# arduino-shield-xyz-stepper-v3.net
KiCad netlist of a schematic drawn in EAGLE
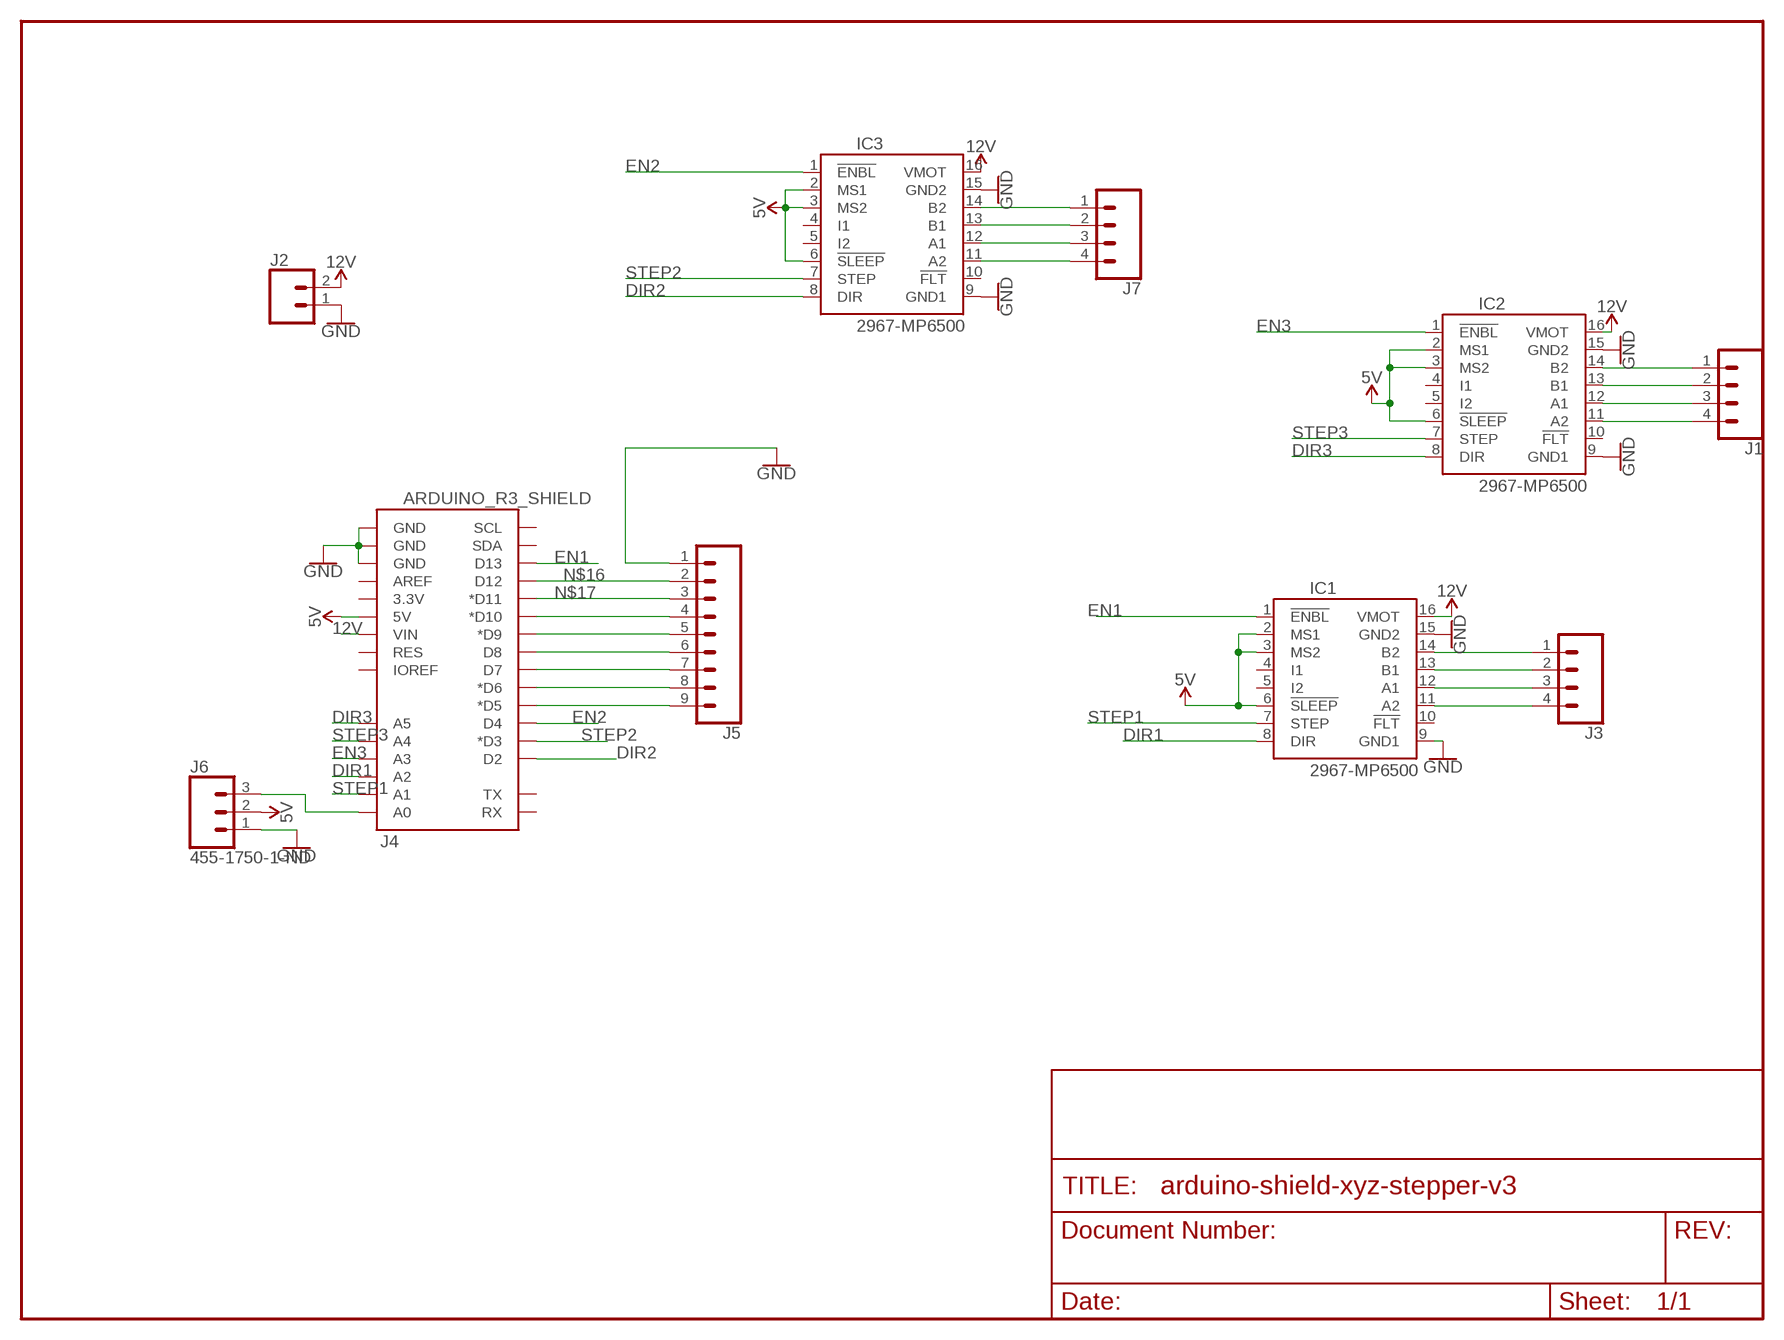
[diagram p0: schematic, sheet 1]

(export (version "E")
  (design (tool "Eeschema 10.0.6"))
  (components
    (comp (ref "IC1")
      (value "2967-MP6500")
      (footprint "eagle-import:MP6500")
      (libsource (lib "eagle-import") (part "2967-MP6500"))
    )
    (comp (ref "IC2")
      (value "2967-MP6500")
      (footprint "eagle-import:MP6500")
      (libsource (lib "eagle-import") (part "2967-MP6500"))
    )
    (comp (ref "IC3")
      (value "2967-MP6500")
      (footprint "eagle-import:MP6500")
      (libsource (lib "eagle-import") (part "2967-MP6500"))
    )
    (comp (ref "J1")
      (value "CONN_04")
      (footprint "eagle-import:1X04")
      (libsource (lib "eagle-import") (part "CONN_04"))
    )
    (comp (ref "J2")
      (value "CONN_02")
      (footprint "eagle-import:1X02")
      (libsource (lib "eagle-import") (part "CONN_02"))
    )
    (comp (ref "J3")
      (value "CONN_04")
      (footprint "eagle-import:1X04")
      (libsource (lib "eagle-import") (part "CONN_04"))
    )
    (comp (ref "J4")
      (value "ARDUINO_R3_SHIELD")
      (footprint "eagle-import:UNO_R3_SHIELD")
      (libsource (lib "eagle-import") (part "ARDUINO_R3_SHIELD"))
    )
    (comp (ref "J5")
      (value "CONN_09")
      (footprint "eagle-import:1X09")
      (libsource (lib "eagle-import") (part "CONN_09"))
    )
    (comp (ref "J6")
      (value "455-1750-1-ND")
      (footprint "eagle-import:1X03")
      (libsource (lib "eagle-import") (part "CONN_03"))
    )
    (comp (ref "J7")
      (value "CONN_04")
      (footprint "eagle-import:1X04")
      (libsource (lib "eagle-import") (part "CONN_04"))
    )
  )
  (nets
    (net (code "1") (name "/DIR1") (class "Default")
      (node (ref "IC1") (pin "8") (pinfunction "DIR_8") (pintype "input"))
      (node (ref "J4") (pin "A2") (pinfunction "A2_A2") (pintype "bidirectional"))
    )
    (net (code "2") (name "/DIR2") (class "Default")
      (node (ref "IC3") (pin "8") (pinfunction "DIR_8") (pintype "input"))
      (node (ref "J4") (pin "D2") (pinfunction "D2_D2") (pintype "bidirectional"))
    )
    (net (code "3") (name "/DIR3") (class "Default")
      (node (ref "IC2") (pin "8") (pinfunction "DIR_8") (pintype "input"))
      (node (ref "J4") (pin "A5") (pinfunction "A5_A5") (pintype "bidirectional"))
    )
    (net (code "4") (name "/EN1") (class "Default")
      (node (ref "IC1") (pin "1") (pinfunction "~{ENBL}_1") (pintype "passive"))
      (node (ref "J4") (pin "D13") (pinfunction "D13_D13") (pintype "bidirectional"))
    )
    (net (code "5") (name "/EN2") (class "Default")
      (node (ref "IC3") (pin "1") (pinfunction "~{ENBL}_1") (pintype "passive"))
      (node (ref "J4") (pin "D4") (pinfunction "D4_D4") (pintype "bidirectional"))
    )
    (net (code "6") (name "/EN3") (class "Default")
      (node (ref "IC2") (pin "1") (pinfunction "~{ENBL}_1") (pintype "passive"))
      (node (ref "J4") (pin "A3") (pinfunction "A3_A3") (pintype "bidirectional"))
    )
    (net (code "7") (name "/N$16") (class "Default")
      (node (ref "J4") (pin "D12") (pinfunction "D12_D12") (pintype "bidirectional"))
      (node (ref "J5") (pin "2") (pinfunction "2_2") (pintype "passive"))
    )
    (net (code "8") (name "/N$17") (class "Default")
      (node (ref "J4") (pin "D11") (pinfunction "*D11_D11") (pintype "bidirectional"))
      (node (ref "J5") (pin "3") (pinfunction "3_3") (pintype "passive"))
    )
    (net (code "9") (name "/STEP1") (class "Default")
      (node (ref "IC1") (pin "7") (pinfunction "STEP_7") (pintype "input"))
      (node (ref "J4") (pin "A1") (pinfunction "A1_A1") (pintype "bidirectional"))
    )
    (net (code "10") (name "/STEP2") (class "Default")
      (node (ref "IC3") (pin "7") (pinfunction "STEP_7") (pintype "input"))
      (node (ref "J4") (pin "D3") (pinfunction "*D3_D3") (pintype "bidirectional"))
    )
    (net (code "11") (name "/STEP3") (class "Default")
      (node (ref "IC2") (pin "7") (pinfunction "STEP_7") (pintype "input"))
      (node (ref "J4") (pin "A4") (pinfunction "A4_A4") (pintype "bidirectional"))
    )
    (net (code "12") (name "5V") (class "Default")
      (node (ref "IC1") (pin "2") (pinfunction "MS1_2") (pintype "passive"))
      (node (ref "IC1") (pin "3") (pinfunction "MS2_3") (pintype "passive"))
      (node (ref "IC1") (pin "6") (pinfunction "~{SLEEP}_6") (pintype "input"))
      (node (ref "IC2") (pin "2") (pinfunction "MS1_2") (pintype "passive"))
      (node (ref "IC2") (pin "3") (pinfunction "MS2_3") (pintype "passive"))
      (node (ref "IC2") (pin "6") (pinfunction "~{SLEEP}_6") (pintype "input"))
      (node (ref "IC3") (pin "2") (pinfunction "MS1_2") (pintype "passive"))
      (node (ref "IC3") (pin "3") (pinfunction "MS2_3") (pintype "passive"))
      (node (ref "IC3") (pin "6") (pinfunction "~{SLEEP}_6") (pintype "input"))
      (node (ref "J4") (pin "5V") (pinfunction "5V_5V") (pintype "bidirectional"))
      (node (ref "J6") (pin "2") (pinfunction "2_2") (pintype "passive"))
    )
    (net (code "13") (name "12V") (class "Default")
      (node (ref "IC1") (pin "16") (pinfunction "VMOT_16") (pintype "power_in"))
      (node (ref "IC2") (pin "16") (pinfunction "VMOT_16") (pintype "power_in"))
      (node (ref "IC3") (pin "16") (pinfunction "VMOT_16") (pintype "power_in"))
      (node (ref "J2") (pin "2") (pinfunction "2_2") (pintype "passive"))
      (node (ref "J4") (pin "VIN") (pinfunction "VIN_VIN") (pintype "bidirectional"))
    )
    (net (code "14") (name "GND") (class "Default")
      (node (ref "IC1") (pin "15") (pinfunction "GND2_15") (pintype "power_in"))
      (node (ref "IC1") (pin "9") (pinfunction "GND1_9") (pintype "power_in"))
      (node (ref "IC2") (pin "15") (pinfunction "GND2_15") (pintype "power_in"))
      (node (ref "IC2") (pin "9") (pinfunction "GND1_9") (pintype "power_in"))
      (node (ref "IC3") (pin "15") (pinfunction "GND2_15") (pintype "power_in"))
      (node (ref "IC3") (pin "9") (pinfunction "GND1_9") (pintype "power_in"))
      (node (ref "J2") (pin "1") (pinfunction "1_1") (pintype "passive"))
      (node (ref "J4") (pin "GND@0") (pinfunction "GND_GND@0") (pintype "bidirectional"))
      (node (ref "J4") (pin "GND@1") (pinfunction "GND_GND@1") (pintype "bidirectional"))
      (node (ref "J4") (pin "GND@2") (pinfunction "GND_GND@2") (pintype "bidirectional"))
      (node (ref "J5") (pin "1") (pinfunction "1_1") (pintype "passive"))
      (node (ref "J6") (pin "1") (pinfunction "1_1") (pintype "passive"))
    )
    (net (code "15") (name "Net-(IC1-A1)") (class "Default")
      (node (ref "IC1") (pin "12") (pinfunction "A1_12") (pintype "output"))
      (node (ref "J3") (pin "3") (pinfunction "3_3") (pintype "passive"))
    )
    (net (code "16") (name "Net-(IC1-A2)") (class "Default")
      (node (ref "IC1") (pin "11") (pinfunction "A2_11") (pintype "output"))
      (node (ref "J3") (pin "4") (pinfunction "4_4") (pintype "passive"))
    )
    (net (code "17") (name "Net-(IC1-B1)") (class "Default")
      (node (ref "IC1") (pin "13") (pinfunction "B1_13") (pintype "output"))
      (node (ref "J3") (pin "2") (pinfunction "2_2") (pintype "passive"))
    )
    (net (code "18") (name "Net-(IC1-B2)") (class "Default")
      (node (ref "IC1") (pin "14") (pinfunction "B2_14") (pintype "output"))
      (node (ref "J3") (pin "1") (pinfunction "1_1") (pintype "passive"))
    )
    (net (code "19") (name "Net-(IC2-A1)") (class "Default")
      (node (ref "IC2") (pin "12") (pinfunction "A1_12") (pintype "output"))
      (node (ref "J1") (pin "3") (pinfunction "3_3") (pintype "passive"))
    )
    (net (code "20") (name "Net-(IC2-A2)") (class "Default")
      (node (ref "IC2") (pin "11") (pinfunction "A2_11") (pintype "output"))
      (node (ref "J1") (pin "4") (pinfunction "4_4") (pintype "passive"))
    )
    (net (code "21") (name "Net-(IC2-B1)") (class "Default")
      (node (ref "IC2") (pin "13") (pinfunction "B1_13") (pintype "output"))
      (node (ref "J1") (pin "2") (pinfunction "2_2") (pintype "passive"))
    )
    (net (code "22") (name "Net-(IC2-B2)") (class "Default")
      (node (ref "IC2") (pin "14") (pinfunction "B2_14") (pintype "output"))
      (node (ref "J1") (pin "1") (pinfunction "1_1") (pintype "passive"))
    )
    (net (code "23") (name "Net-(IC3-A1)") (class "Default")
      (node (ref "IC3") (pin "12") (pinfunction "A1_12") (pintype "output"))
      (node (ref "J7") (pin "3") (pinfunction "3_3") (pintype "passive"))
    )
    (net (code "24") (name "Net-(IC3-A2)") (class "Default")
      (node (ref "IC3") (pin "11") (pinfunction "A2_11") (pintype "output"))
      (node (ref "J7") (pin "4") (pinfunction "4_4") (pintype "passive"))
    )
    (net (code "25") (name "Net-(IC3-B1)") (class "Default")
      (node (ref "IC3") (pin "13") (pinfunction "B1_13") (pintype "output"))
      (node (ref "J7") (pin "2") (pinfunction "2_2") (pintype "passive"))
    )
    (net (code "26") (name "Net-(IC3-B2)") (class "Default")
      (node (ref "IC3") (pin "14") (pinfunction "B2_14") (pintype "output"))
      (node (ref "J7") (pin "1") (pinfunction "1_1") (pintype "passive"))
    )
    (net (code "27") (name "Net-(J4-*D5)") (class "Default")
      (node (ref "J4") (pin "D5") (pinfunction "*D5_D5") (pintype "bidirectional"))
      (node (ref "J5") (pin "9") (pinfunction "9_9") (pintype "passive"))
    )
    (net (code "28") (name "Net-(J4-*D6)") (class "Default")
      (node (ref "J4") (pin "D6") (pinfunction "*D6_D6") (pintype "bidirectional"))
      (node (ref "J5") (pin "8") (pinfunction "8_8") (pintype "passive"))
    )
    (net (code "29") (name "Net-(J4-*D9)") (class "Default")
      (node (ref "J4") (pin "D9") (pinfunction "*D9_D9") (pintype "bidirectional"))
      (node (ref "J5") (pin "5") (pinfunction "5_5") (pintype "passive"))
    )
    (net (code "30") (name "Net-(J4-*D10)") (class "Default")
      (node (ref "J4") (pin "D10") (pinfunction "*D10_D10") (pintype "bidirectional"))
      (node (ref "J5") (pin "4") (pinfunction "4_4") (pintype "passive"))
    )
    (net (code "31") (name "Net-(J4-PadA0)") (class "Default")
      (node (ref "J4") (pin "A0") (pinfunction "A0_A0") (pintype "bidirectional"))
      (node (ref "J6") (pin "3") (pinfunction "3_3") (pintype "passive"))
    )
    (net (code "32") (name "Net-(J4-PadD7)") (class "Default")
      (node (ref "J4") (pin "D7") (pinfunction "D7_D7") (pintype "bidirectional"))
      (node (ref "J5") (pin "7") (pinfunction "7_7") (pintype "passive"))
    )
    (net (code "33") (name "Net-(J4-PadD8)") (class "Default")
      (node (ref "J4") (pin "D8") (pinfunction "D8_D8") (pintype "bidirectional"))
      (node (ref "J5") (pin "6") (pinfunction "6_6") (pintype "passive"))
    )
    (net (code "34") (name "unconnected-(IC1-I1-Pad4)") (class "Default")
      (node (ref "IC1") (pin "4") (pinfunction "I1_4") (pintype "passive"))
    )
    (net (code "35") (name "unconnected-(IC1-I2-Pad5)") (class "Default")
      (node (ref "IC1") (pin "5") (pinfunction "I2_5") (pintype "passive"))
    )
    (net (code "36") (name "unconnected-(IC1-~{FLT}-Pad10)") (class "Default")
      (node (ref "IC1") (pin "10") (pinfunction "~{FLT}_10") (pintype "open_collector"))
    )
    (net (code "37") (name "unconnected-(IC2-I1-Pad4)") (class "Default")
      (node (ref "IC2") (pin "4") (pinfunction "I1_4") (pintype "passive"))
    )
    (net (code "38") (name "unconnected-(IC2-I2-Pad5)") (class "Default")
      (node (ref "IC2") (pin "5") (pinfunction "I2_5") (pintype "passive"))
    )
    (net (code "39") (name "unconnected-(IC2-~{FLT}-Pad10)") (class "Default")
      (node (ref "IC2") (pin "10") (pinfunction "~{FLT}_10") (pintype "open_collector"))
    )
    (net (code "40") (name "unconnected-(IC3-I1-Pad4)") (class "Default")
      (node (ref "IC3") (pin "4") (pinfunction "I1_4") (pintype "passive"))
    )
    (net (code "41") (name "unconnected-(IC3-I2-Pad5)") (class "Default")
      (node (ref "IC3") (pin "5") (pinfunction "I2_5") (pintype "passive"))
    )
    (net (code "42") (name "unconnected-(IC3-~{FLT}-Pad10)") (class "Default")
      (node (ref "IC3") (pin "10") (pinfunction "~{FLT}_10") (pintype "open_collector"))
    )
    (net (code "43") (name "unconnected-(J4-Pad3.3V)") (class "Default")
      (node (ref "J4") (pin "3.3V") (pinfunction "3.3V_3.3V") (pintype "bidirectional"))
    )
    (net (code "44") (name "unconnected-(J4-PadAREF)") (class "Default")
      (node (ref "J4") (pin "AREF") (pinfunction "AREF_AREF") (pintype "bidirectional"))
    )
    (net (code "45") (name "unconnected-(J4-PadIOREF)") (class "Default")
      (node (ref "J4") (pin "IOREF") (pinfunction "IOREF_IOREF") (pintype "bidirectional"))
    )
    (net (code "46") (name "unconnected-(J4-PadRES)") (class "Default")
      (node (ref "J4") (pin "RES") (pinfunction "RES_RES") (pintype "bidirectional"))
    )
    (net (code "47") (name "unconnected-(J4-PadRX)") (class "Default")
      (node (ref "J4") (pin "RX") (pinfunction "RX_RX") (pintype "bidirectional"))
    )
    (net (code "48") (name "unconnected-(J4-PadSCL)") (class "Default")
      (node (ref "J4") (pin "SCL") (pinfunction "SCL_SCL") (pintype "bidirectional"))
    )
    (net (code "49") (name "unconnected-(J4-PadSDA)") (class "Default")
      (node (ref "J4") (pin "SDA") (pinfunction "SDA_SDA") (pintype "bidirectional"))
    )
    (net (code "50") (name "unconnected-(J4-PadTX)") (class "Default")
      (node (ref "J4") (pin "TX") (pinfunction "TX_TX") (pintype "bidirectional"))
    )
  )
)
